# TSOC_WaterSensor.net
KiCad netlist of a schematic drawn in EAGLE
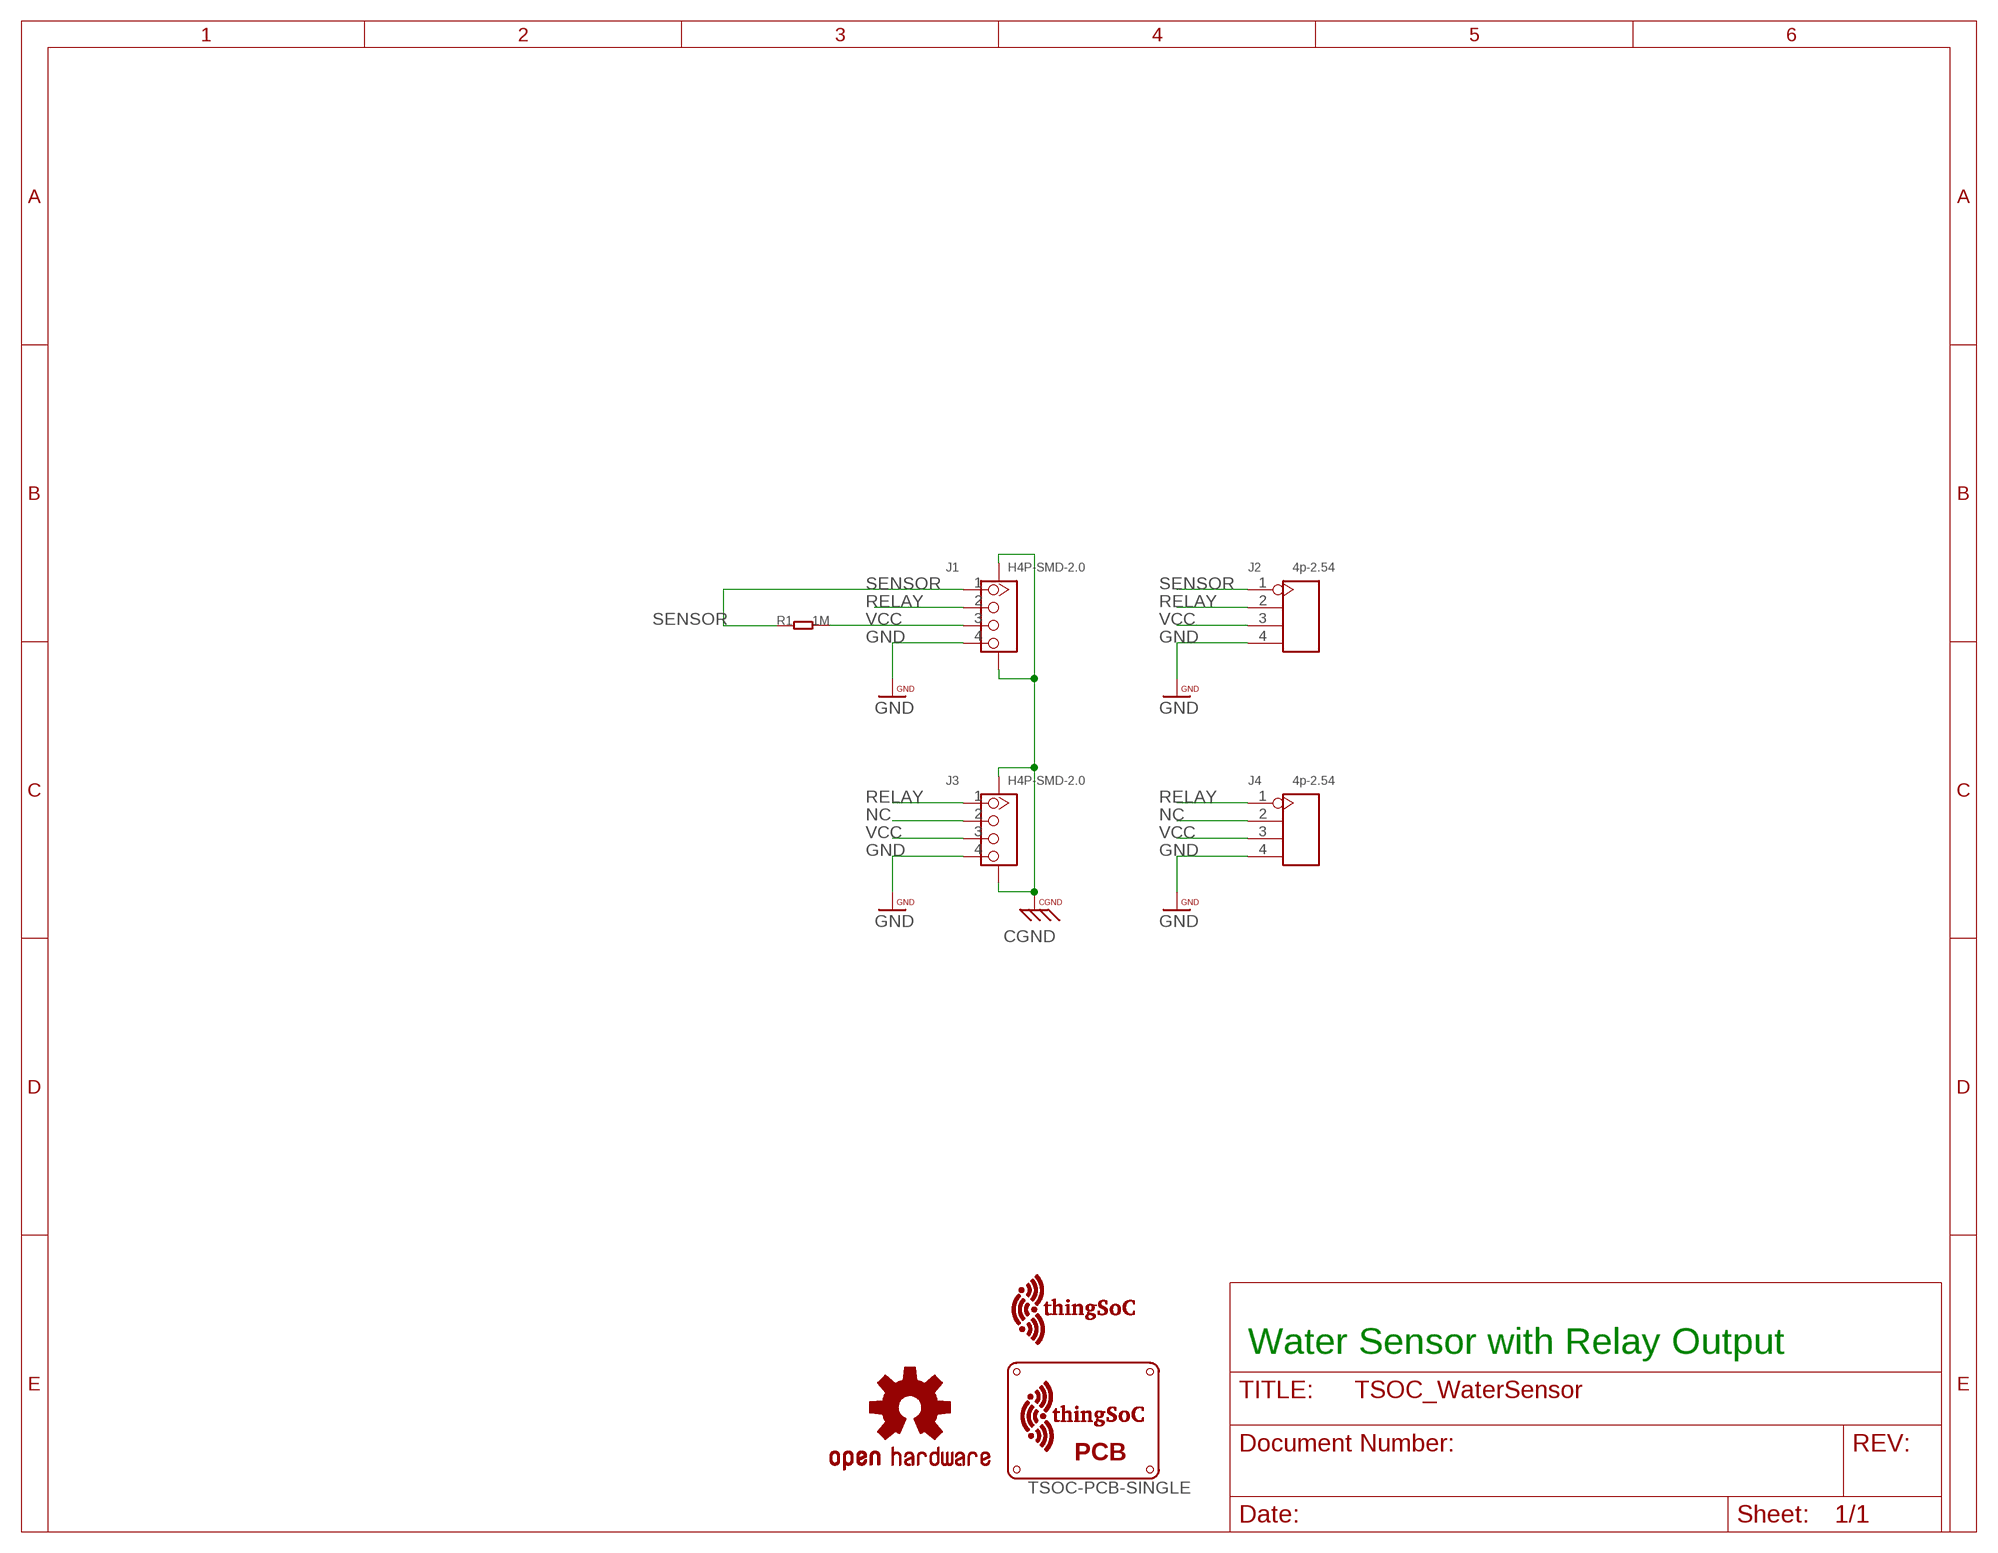
[diagram p0: schematic, sheet 1]

(export (version "E")
  (design (tool "Eeschema 10.0.6"))
  (components
    (comp (ref "J1")
      (value "H4P-SMD-2.0")
      (footprint "eagle-import:HW4-SMD-2.0")
      (libsource (lib "eagle-import") (part "GROVE-CONNECTOR-SMD(4+2P-2.0)"))
    )
    (comp (ref "J2")
      (value "4p-2.54")
      (footprint "eagle-import:H4-2.54")
      (fields (field (name "MPN") "P125-1104A0BS116A1"))
      (libsource (lib "eagle-import") (part "DIP-BLACK-MALE-HEADER-VERT(4P-2.54)"))
    )
    (comp (ref "J3")
      (value "H4P-SMD-2.0")
      (footprint "eagle-import:HW4-SMD-2.0")
      (libsource (lib "eagle-import") (part "GROVE-CONNECTOR-SMD(4+2P-2.0)"))
    )
    (comp (ref "J4")
      (value "4p-2.54")
      (footprint "eagle-import:H4-2.54")
      (fields (field (name "MPN") "P125-1104A0BS116A1"))
      (libsource (lib "eagle-import") (part "DIP-BLACK-MALE-HEADER-VERT(4P-2.54)"))
    )
    (comp (ref "R1")
      (value "1M")
      (footprint "eagle-import:0603")
      (libsource (lib "eagle-import") (part "R0603"))
    )
    (comp (ref "U$1")
      (value "OSHW_LOGO_SYMM")
      (footprint "eagle-import:OSHW_LOGO_MED_SYM")
      (libsource (lib "eagle-import") (part "OSHW_LOGO_SYMM"))
    )
    (comp (ref "U$2")
      (value "TSOC-LOGO-LRG")
      (footprint "eagle-import:TSOC-LOGO-LRG")
      (libsource (lib "eagle-import") (part "TSOC-LOGO-LRG"))
    )
    (comp (ref "U$3")
      (value "TSOC-PCB-SINGLE")
      (footprint "eagle-import:TSOC-BB-BRD-DIM")
      (libsource (lib "eagle-import") (part "TSOC-PCB-SINGLE"))
    )
  )
  (nets
    (net (code "1") (name "/NC") (class "Default")
      (node (ref "J3") (pin "2") (pinfunction "2_2") (pintype "bidirectional"))
      (node (ref "J4") (pin "2") (pinfunction "P$2_2") (pintype "bidirectional"))
    )
    (net (code "2") (name "/RELAY") (class "Default")
      (node (ref "J1") (pin "2") (pinfunction "2_2") (pintype "bidirectional"))
      (node (ref "J2") (pin "2") (pinfunction "P$2_2") (pintype "bidirectional"))
      (node (ref "J3") (pin "1") (pinfunction "1_1") (pintype "bidirectional"))
      (node (ref "J4") (pin "1") (pinfunction "P$1_1") (pintype "bidirectional"))
    )
    (net (code "3") (name "/SENSOR") (class "Default")
      (node (ref "J1") (pin "1") (pinfunction "1_1") (pintype "bidirectional"))
      (node (ref "J2") (pin "1") (pinfunction "P$1_1") (pintype "bidirectional"))
      (node (ref "R1") (pin "1") (pinfunction "1_1") (pintype "bidirectional"))
    )
    (net (code "4") (name "/VCC") (class "Default")
      (node (ref "J1") (pin "3") (pinfunction "3_3") (pintype "bidirectional"))
      (node (ref "J2") (pin "3") (pinfunction "P$3_3") (pintype "bidirectional"))
      (node (ref "J3") (pin "3") (pinfunction "3_3") (pintype "bidirectional"))
      (node (ref "J4") (pin "3") (pinfunction "P$3_3") (pintype "bidirectional"))
      (node (ref "R1") (pin "2") (pinfunction "2_2") (pintype "bidirectional"))
    )
    (net (code "5") (name "CGND") (class "Default")
      (node (ref "J1") (pin "SS1") (pinfunction "SS1_SS1") (pintype "bidirectional"))
      (node (ref "J1") (pin "SS2") (pinfunction "SS2_SS2") (pintype "bidirectional"))
      (node (ref "J3") (pin "SS1") (pinfunction "SS1_SS1") (pintype "bidirectional"))
      (node (ref "J3") (pin "SS2") (pinfunction "SS2_SS2") (pintype "bidirectional"))
    )
    (net (code "6") (name "GND") (class "Default")
      (node (ref "J1") (pin "4") (pinfunction "4_4") (pintype "bidirectional"))
      (node (ref "J2") (pin "4") (pinfunction "P$4_4") (pintype "bidirectional"))
      (node (ref "J3") (pin "4") (pinfunction "4_4") (pintype "bidirectional"))
      (node (ref "J4") (pin "4") (pinfunction "P$4_4") (pintype "bidirectional"))
    )
  )
)
